# Main.net
KiCad netlist of a schematic drawn in Altium Designer
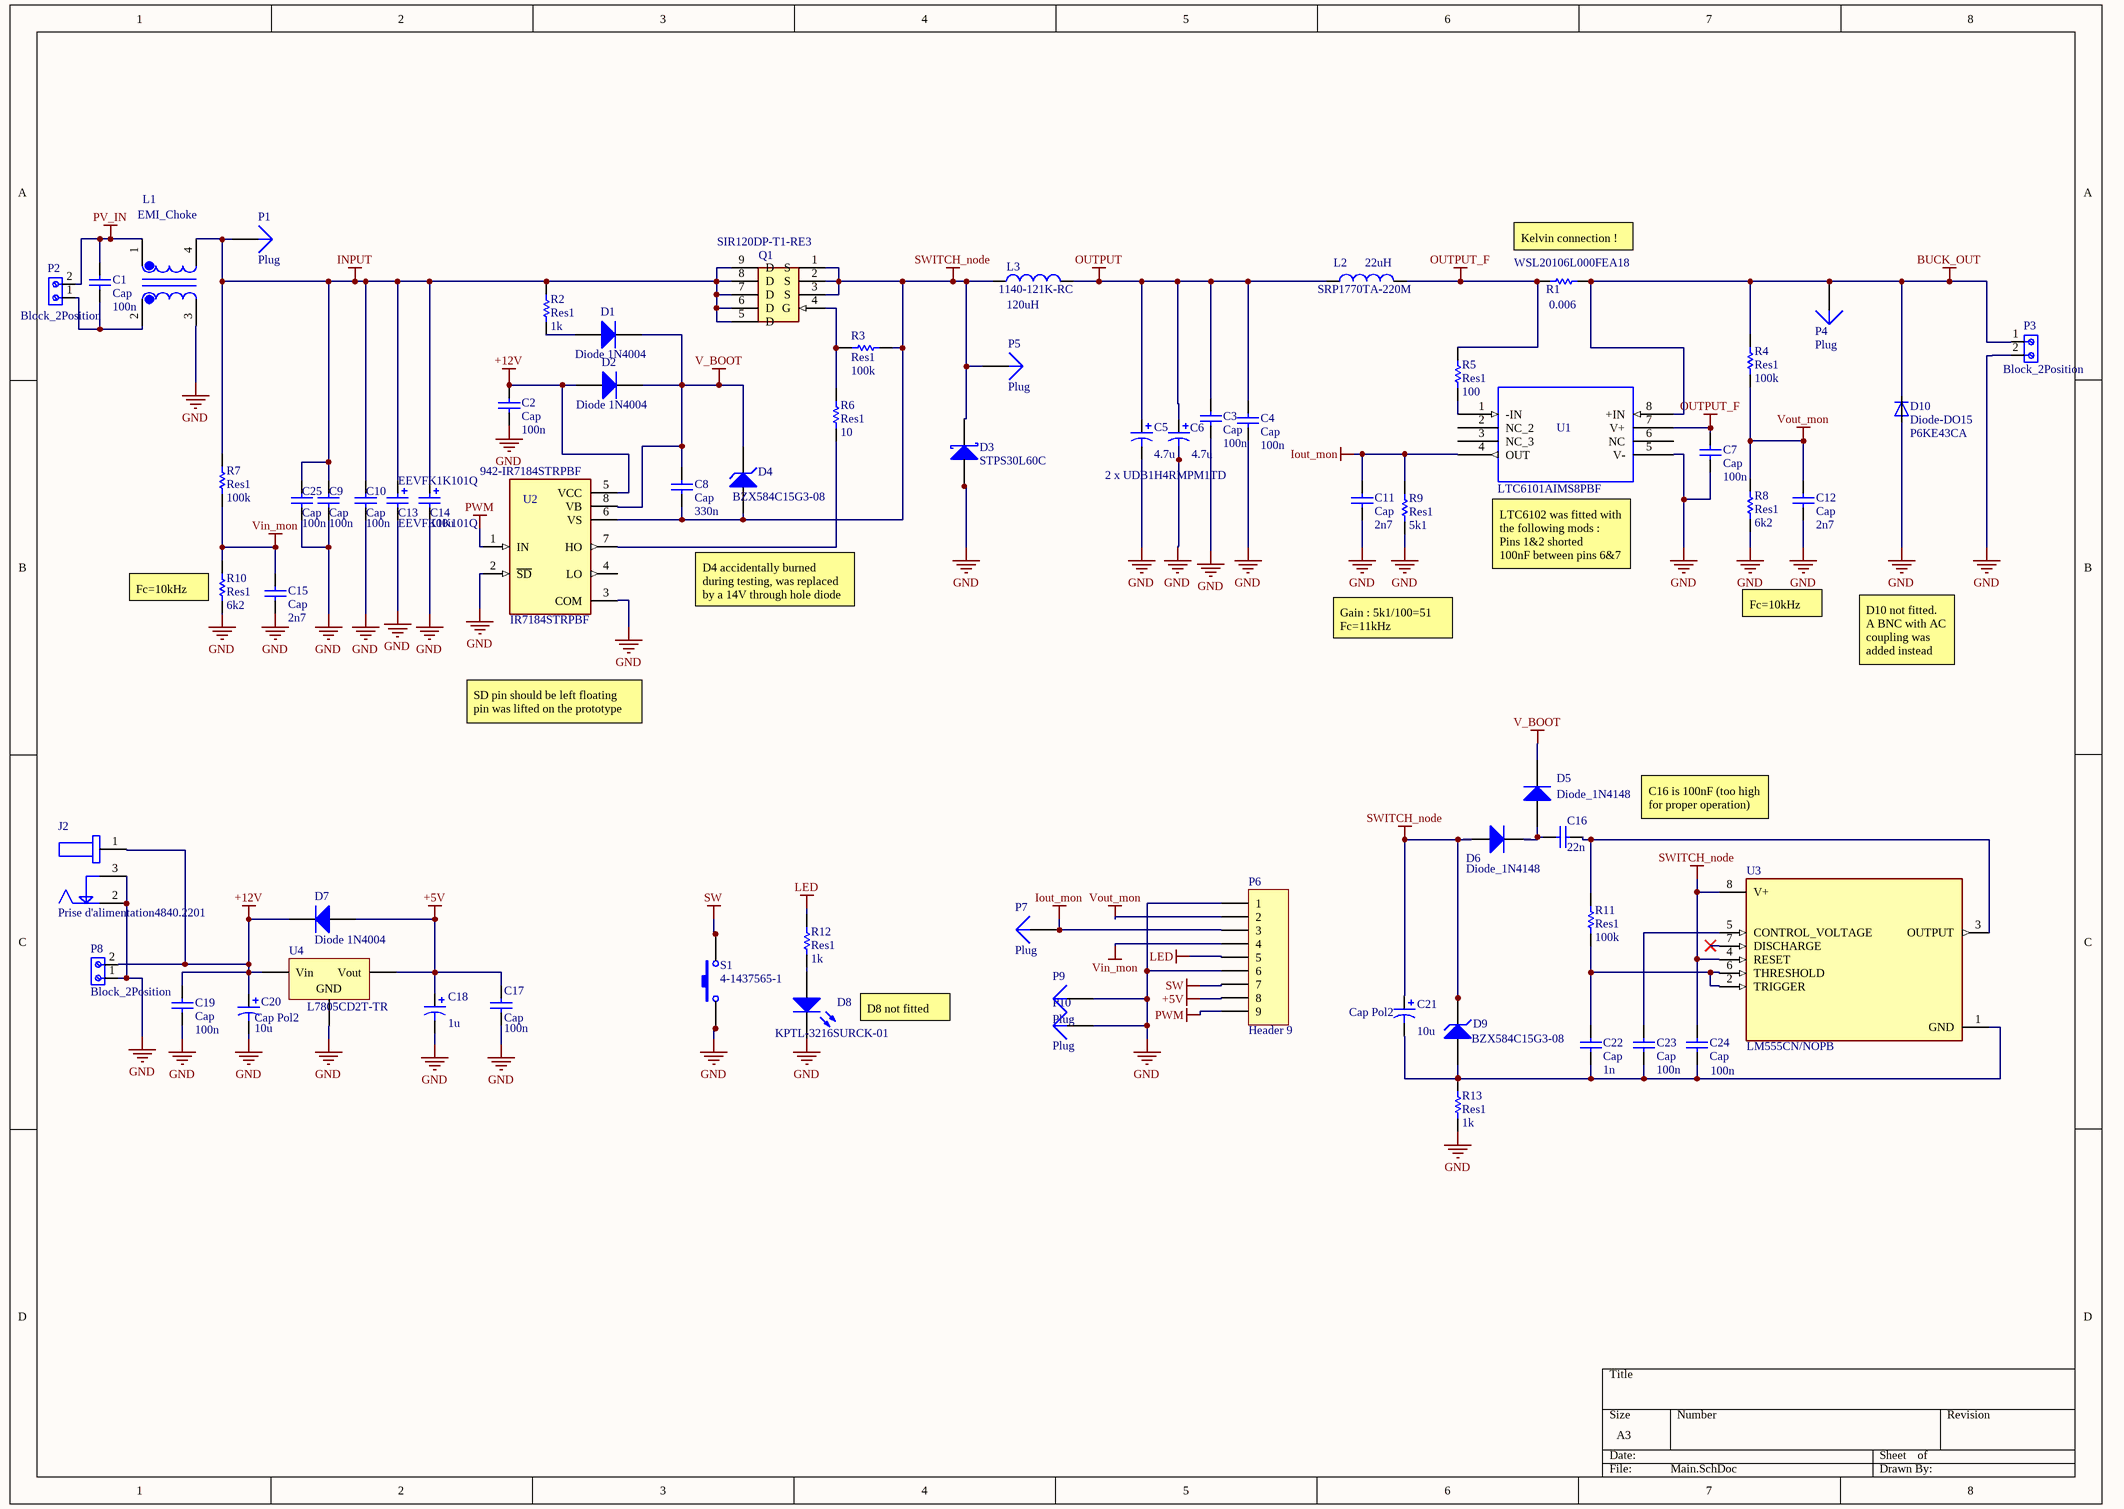
[diagram p0: Main.SchDoc]

(export (version "E")
  (design (tool "Eeschema 10.0.6"))
  (components
    (comp (ref "C1")
      (value "Cap")
      (footprint "C0805")
      (description "Capacitor")
      (fields (field (name "ALTIUM_VALUE") "100n") (field (name "PUBLISHER") "Altium Limited"))
      (libsource (lib "Buck") (part "Cap"))
    )
    (comp (ref "C2")
      (value "Cap")
      (footprint "C0805")
      (description "Capacitor")
      (fields (field (name "ALTIUM_VALUE") "100n") (field (name "PUBLISHER") "Altium Limited"))
      (libsource (lib "Buck") (part "Cap"))
    )
    (comp (ref "C3")
      (value "Cap")
      (footprint "C0805")
      (description "Capacitor")
      (fields (field (name "ALTIUM_VALUE") "100n") (field (name "PUBLISHER") "Altium Limited"))
      (libsource (lib "Buck") (part "Cap"))
    )
    (comp (ref "C4")
      (value "Cap")
      (footprint "C0805")
      (description "Capacitor")
      (fields (field (name "ALTIUM_VALUE") "100n") (field (name "PUBLISHER") "Altium Limited"))
      (libsource (lib "Buck") (part "Cap"))
    )
    (comp (ref "C5")
      (value "4.7u")
      (footprint "C1-C2")
      (fields (field (name "Comment") "2 x UDB1H4RMPM1TD") (field (name "PUBLISHER") "Altium Limited"))
      (libsource (lib "Buck") (part "Cap Pol2"))
    )
    (comp (ref "C6")
      (value "2 x UDB1H4RMPM1TD")
      (footprint "C1-C2")
      (fields (field (name "ALTIUM_VALUE") "4.7u") (field (name "PUBLISHER") "Altium Limited"))
      (libsource (lib "Buck") (part "Cap Pol2"))
    )
    (comp (ref "C7")
      (value "Cap")
      (footprint "C0805")
      (description "Capacitor")
      (fields (field (name "ALTIUM_VALUE") "100n") (field (name "PUBLISHER") "Altium Limited"))
      (libsource (lib "Buck") (part "Cap"))
    )
    (comp (ref "C8")
      (value "Cap")
      (footprint "C0805")
      (description "Capacitor")
      (fields (field (name "ALTIUM_VALUE") "330n") (field (name "PUBLISHER") "Altium Limited"))
      (libsource (lib "Buck") (part "Cap_2"))
    )
    (comp (ref "C9")
      (value "Cap")
      (footprint "C0805")
      (description "Capacitor")
      (fields (field (name "ALTIUM_VALUE") "100n") (field (name "PUBLISHER") "Altium Limited"))
      (libsource (lib "Buck") (part "Cap"))
    )
    (comp (ref "C10")
      (value "Cap")
      (footprint "C0805")
      (description "Capacitor")
      (fields (field (name "ALTIUM_VALUE") "100n") (field (name "PUBLISHER") "Altium Limited"))
      (libsource (lib "Buck") (part "Cap"))
    )
    (comp (ref "C11")
      (value "Cap")
      (footprint "C0805")
      (description "Capacitor")
      (fields (field (name "ALTIUM_VALUE") "2n7") (field (name "PUBLISHER") "Altium Limited"))
      (libsource (lib "Buck") (part "Cap_1"))
    )
    (comp (ref "C12")
      (value "Cap")
      (footprint "C0805")
      (description "Capacitor")
      (fields (field (name "ALTIUM_VALUE") "2n7") (field (name "PUBLISHER") "Altium Limited"))
      (libsource (lib "Buck") (part "Cap_1"))
    )
    (comp (ref "C13")
      (value "EEVFK1K101Q")
      (footprint "C_Pol_EEV-FK1K101Q")
      (description "Polarized Capacitor (Axial)")
      (fields (field (name "PUBLISHER") "Altium Limited"))
      (libsource (lib "Buck") (part "Cap Pol2_1"))
    )
    (comp (ref "C14")
      (value "EEVFK1K101Q")
      (footprint "C_Pol_EEV-FK1K101Q")
      (description "Polarized Capacitor (Axial)")
      (fields (field (name "ALTIUM_VALUE") "100u") (field (name "PUBLISHER") "Altium Limited"))
      (libsource (lib "Buck") (part "Cap Pol2_1"))
    )
    (comp (ref "C15")
      (value "Cap")
      (footprint "C0805")
      (description "Capacitor")
      (fields (field (name "ALTIUM_VALUE") "2n7") (field (name "PUBLISHER") "Altium Limited"))
      (libsource (lib "Buck") (part "Cap_1"))
    )
    (comp (ref "C16") (value "22n") (footprint "C0805") (libsource (lib "Buck") (part "Cap_22n")))
    (comp (ref "C17")
      (value "Cap")
      (footprint "C0805")
      (description "Capacitor")
      (fields (field (name "ALTIUM_VALUE") "100n") (field (name "PUBLISHER") "Altium Limited"))
      (libsource (lib "Buck") (part "Cap"))
    )
    (comp (ref "C18")
      (value "1u")
      (footprint "C0805")
      (fields (field (name "VALEUR") "1u"))
      (libsource (lib "Buck") (part "C_4"))
    )
    (comp (ref "C19")
      (value "Cap")
      (footprint "C0805")
      (description "Capacitor")
      (fields (field (name "ALTIUM_VALUE") "100n") (field (name "PUBLISHER") "Altium Limited"))
      (libsource (lib "Buck") (part "Cap"))
    )
    (comp (ref "C20")
      (value "Cap Pol2")
      (footprint "C_10u")
      (description "Polarized Capacitor (Axial)")
      (fields (field (name "ALTIUM_VALUE") "10u") (field (name "PUBLISHER") "Altium Limited"))
      (libsource (lib "Buck") (part "Cap Pol2_2"))
    )
    (comp (ref "C21")
      (value "Cap Pol2")
      (footprint "C_10u")
      (description "Polarized Capacitor (Axial)")
      (fields (field (name "ALTIUM_VALUE") "10u") (field (name "PUBLISHER") "Altium Limited"))
      (libsource (lib "Buck") (part "Cap Pol2_2"))
    )
    (comp (ref "C22")
      (value "Cap")
      (footprint "C0805")
      (description "Capacitor")
      (fields (field (name "ALTIUM_VALUE") "1n") (field (name "PUBLISHER") "Altium Limited"))
      (libsource (lib "Buck") (part "Cap_3"))
    )
    (comp (ref "C23")
      (value "Cap")
      (footprint "C0805")
      (description "Capacitor")
      (fields (field (name "ALTIUM_VALUE") "100n") (field (name "PUBLISHER") "Altium Limited"))
      (libsource (lib "Buck") (part "Cap"))
    )
    (comp (ref "C24")
      (value "Cap")
      (footprint "C0805")
      (description "Capacitor")
      (fields (field (name "ALTIUM_VALUE") "100n") (field (name "PUBLISHER") "Altium Limited"))
      (libsource (lib "Buck") (part "Cap"))
    )
    (comp (ref "C25")
      (value "Cap")
      (footprint "C0805")
      (description "Capacitor")
      (fields (field (name "ALTIUM_VALUE") "100n") (field (name "PUBLISHER") "Altium Limited"))
      (libsource (lib "Buck") (part "Cap"))
    )
    (comp (ref "D1")
      (value "Diode 1N4004")
      (footprint "diode_1N4004")
      (description "1 Amp General Purpose Rectifier")
      (fields (field (name "PUBLISHER") "Altium Limited"))
      (libsource (lib "Buck") (part "Diode 1N4004"))
    )
    (comp (ref "D2")
      (value "Diode 1N4004")
      (footprint "diode_1N4004")
      (description "1 Amp General Purpose Rectifier")
      (fields (field (name "PUBLISHER") "Altium Limited"))
      (libsource (lib "Buck") (part "Diode 1N4004"))
    )
    (comp (ref "D3")
      (value "STPS30L60C")
      (footprint "Diode_Scho")
      (description "Schottky Diode")
      (fields (field (name "PUBLISHER") "Altium Limited"))
      (libsource (lib "Buck") (part "D Schottky"))
    )
    (comp (ref "D4")
      (value "BZX584C15G3-08")
      (footprint "SOT-523")
      (description "Zener Diode 15V")
      (fields (field (name "PUBLISHER") "Altium Limited"))
      (libsource (lib "Buck") (part "D Zener"))
    )
    (comp (ref "D5")
      (value "Diode_1N4148")
      (footprint "diode_1N4004")
      (libsource (lib "Buck") (part "Diode_1N4148"))
    )
    (comp (ref "D6")
      (value "Diode_1N4148")
      (footprint "diode_1N4004")
      (libsource (lib "Buck") (part "Diode_1N4148"))
    )
    (comp (ref "D7")
      (value "Diode 1N4004")
      (footprint "diode_1N4004")
      (description "1 Amp General Purpose Rectifier")
      (fields (field (name "PUBLISHER") "Altium Limited"))
      (libsource (lib "Buck") (part "Diode 1N4004"))
    )
    (comp (ref "D8")
      (value "KPTL-3216SURCK-01")
      (footprint "LED")
      (description "Typical RED, GREEN, YELLOW, AMBER GaAs LED")
      (fields (field (name "PUBLISHER") "Altium Limited"))
      (libsource (lib "Buck") (part "LED2"))
    )
    (comp (ref "D9")
      (value "BZX584C15G3-08")
      (footprint "SOT-523")
      (description "Zener Diode 15V")
      (fields (field (name "PUBLISHER") "Altium Limited"))
      (libsource (lib "Buck") (part "D Zener"))
    )
    (comp (ref "D10")
      (value "Diode-DO15")
      (footprint "DO15")
      (description "P6KE43CA")
      (fields (field (name "REF") "P6KE43CA"))
      (libsource (lib "Buck") (part "Diode-DO15"))
    )
    (comp (ref "J2")
      (value "Prise d'alimentation4840.2201")
      (footprint "Prise d'alimentation4840.2201")
      (libsource (lib "Buck") (part "Prise d'alimentation4840.2201"))
    )
    (comp (ref "L1")
      (value "EMI_Choke")
      (footprint "EMI_Choke")
      (description "1mH 20A")
      (libsource (lib "Buck") (part "EMI_Choke"))
    )
    (comp (ref "L2")
      (value "SRP1770TA-220M")
      (footprint "SRP1770TA-220M")
      (fields (field (name "ALTIUM_VALUE") "22uH"))
      (libsource (lib "Buck") (part "SRP1770TA-220M"))
    )
    (comp (ref "L3")
      (value "1140-121K-RC")
      (footprint "L_120")
      (fields (field (name "ALTIUM_VALUE") "120uH") (field (name "PUBLISHER") "Altium Limited"))
      (libsource (lib "Buck") (part "Inductor"))
    )
    (comp (ref "P1")
      (value "Plug")
      (footprint "PIN1")
      (fields (field (name "PUBLISHER") "Altium Limited"))
      (libsource (lib "Miscellaneous Connectors") (part "Plug"))
    )
    (comp (ref "P2")
      (value "Block_2Position")
      (footprint "Block_2Position")
      (libsource (lib "Buck") (part "Block_2Position"))
    )
    (comp (ref "P3")
      (value "Block_2Position")
      (footprint "Block_2Position")
      (libsource (lib "Buck") (part "Block_2Position"))
    )
    (comp (ref "P4")
      (value "Plug")
      (footprint "PIN1")
      (fields (field (name "PUBLISHER") "Altium Limited"))
      (libsource (lib "Miscellaneous Connectors") (part "Plug"))
    )
    (comp (ref "P5")
      (value "Plug")
      (footprint "PIN1")
      (fields (field (name "PUBLISHER") "Altium Limited"))
      (libsource (lib "Miscellaneous Connectors") (part "Plug"))
    )
    (comp (ref "P6")
      (value "Header 9")
      (footprint "HDR1X9")
      (description "Header, 9-Pin")
      (fields (field (name "PUBLISHER") "Altium Limited"))
      (libsource (lib "Buck") (part "Header 9"))
    )
    (comp (ref "P7")
      (value "Plug")
      (footprint "PIN1")
      (fields (field (name "PUBLISHER") "Altium Limited"))
      (libsource (lib "Miscellaneous Connectors") (part "Plug"))
    )
    (comp (ref "P8")
      (value "Block_2Position")
      (footprint "Block_2Position")
      (libsource (lib "Buck") (part "Block_2Position"))
    )
    (comp (ref "P9")
      (value "Plug")
      (footprint "PIN1")
      (fields (field (name "PUBLISHER") "Altium Limited"))
      (libsource (lib "Miscellaneous Connectors") (part "Plug"))
    )
    (comp (ref "P10")
      (value "Plug")
      (footprint "PIN1")
      (fields (field (name "PUBLISHER") "Altium Limited"))
      (libsource (lib "Miscellaneous Connectors") (part "Plug"))
    )
    (comp (ref "Q1")
      (value "SIR120DP-T1-RE3")
      (footprint "MOFET_SIR120DP-T1-RE3")
      (libsource (lib "Buck") (part "SIR120DP-T1-RE3"))
    )
    (comp (ref "R1")
      (value "WSL20106L000FEA18")
      (footprint "R0.006")
      (description "Resistor")
      (fields (field (name "ALTIUM_VALUE") "0.006") (field (name "PUBLISHER") "Altium Limited"))
      (libsource (lib "Buck") (part "Res1_2"))
    )
    (comp (ref "R2")
      (value "Res1")
      (footprint "R0805")
      (description "Resistor")
      (fields (field (name "ALTIUM_VALUE") "1k") (field (name "PUBLISHER") "Altium Limited"))
      (libsource (lib "Buck") (part "Res1_6"))
    )
    (comp (ref "R3")
      (value "Res1")
      (footprint "R0805")
      (description "Resistor")
      (fields (field (name "ALTIUM_VALUE") "100k") (field (name "PUBLISHER") "Altium Limited"))
      (libsource (lib "Buck") (part "Res1"))
    )
    (comp (ref "R4")
      (value "Res1")
      (footprint "R0805")
      (description "Resistor")
      (fields (field (name "ALTIUM_VALUE") "100k") (field (name "PUBLISHER") "Altium Limited"))
      (libsource (lib "Buck") (part "Res1"))
    )
    (comp (ref "R5")
      (value "Res1")
      (footprint "R0805")
      (description "Resistor")
      (fields (field (name "ALTIUM_VALUE") "100") (field (name "PUBLISHER") "Altium Limited"))
      (libsource (lib "Buck") (part "Res1_3"))
    )
    (comp (ref "R6")
      (value "Res1")
      (footprint "R0805")
      (description "Resistor")
      (fields (field (name "ALTIUM_VALUE") "10") (field (name "PUBLISHER") "Altium Limited"))
      (libsource (lib "Buck") (part "Res1_5"))
    )
    (comp (ref "R7")
      (value "Res1")
      (footprint "R0805")
      (description "Resistor")
      (fields (field (name "ALTIUM_VALUE") "100k") (field (name "PUBLISHER") "Altium Limited"))
      (libsource (lib "Buck") (part "Res1"))
    )
    (comp (ref "R8")
      (value "Res1")
      (footprint "R0805")
      (description "Resistor")
      (fields (field (name "ALTIUM_VALUE") "6k2") (field (name "PUBLISHER") "Altium Limited"))
      (libsource (lib "Buck") (part "Res1_1"))
    )
    (comp (ref "R9")
      (value "Res1")
      (footprint "R0805")
      (description "Resistor")
      (fields (field (name "ALTIUM_VALUE") "5k1") (field (name "PUBLISHER") "Altium Limited"))
      (libsource (lib "Buck") (part "Res1_4"))
    )
    (comp (ref "R10")
      (value "Res1")
      (footprint "R0805")
      (description "Resistor")
      (fields (field (name "ALTIUM_VALUE") "6k2") (field (name "PUBLISHER") "Altium Limited"))
      (libsource (lib "Buck") (part "Res1_1"))
    )
    (comp (ref "R11")
      (value "Res1")
      (footprint "R0805")
      (description "Resistor")
      (fields (field (name "ALTIUM_VALUE") "100k") (field (name "PUBLISHER") "Altium Limited"))
      (libsource (lib "Buck") (part "Res1"))
    )
    (comp (ref "R12")
      (value "Res1")
      (footprint "R0805")
      (description "Resistor")
      (fields (field (name "ALTIUM_VALUE") "1k") (field (name "PUBLISHER") "Altium Limited"))
      (libsource (lib "Buck") (part "Res1_6"))
    )
    (comp (ref "R13")
      (value "Res1")
      (footprint "R0805")
      (description "Resistor")
      (fields (field (name "ALTIUM_VALUE") "1k") (field (name "PUBLISHER") "Altium Limited"))
      (libsource (lib "Buck") (part "Res1_6"))
    )
    (comp (ref "S1")
      (value "4-1437565-1")
      (footprint "Switch")
      (description "Switch")
      (fields (field (name "PUBLISHER") "Altium Limited"))
      (libsource (lib "Buck") (part "SW-PB"))
    )
    (comp (ref "U1")
      (value "LTC6101AIMS8PBF")
      (footprint "LTC6101AIMS8#PBF")
      (description "SP Amp Current Sense Amp Single 60V Automotive 8-Pin MSOP Tube")
      (fields (field (name "MP") "LTC6101AIMS8#PBF") (field (name "MF") "Analog Devices"))
      (libsource (lib "Buck") (part "LTC6101AIMS8PBF"))
    )
    (comp (ref "U2")
      (value "IR7184STRPBF")
      (footprint "IR7184STRPBF")
      (fields
        (field (name "MF") "Infineon Technologies")
        (field (name "SUPPLIER PART NUMBER 1") "942-IR7184STRPBF")
      )
      (libsource (lib "Buck") (part "IR7184STRPBF"))
    )
    (comp (ref "U3")
      (value "LM555CN/NOPB")
      (footprint "LM555CN/NOPB")
      (libsource (lib "Buck") (part "LM555CN/NOPB"))
    )
    (comp (ref "U4")
      (value "L7805CD2T-TR")
      (footprint "Volt_Reg")
      (description "Voltage Regulator")
      (fields (field (name "PUBLISHER") "Altium Limited"))
      (libsource (lib "Buck") (part "Volt Reg"))
    )
  )
  (nets
    (net (code "1") (name "+5V") (class "Default")
      (node (ref "C17") (pin "2") (pinfunction "2_2") (pintype "passive"))
      (node (ref "C18") (pin "1") (pinfunction "1_1") (pintype "passive"))
      (node (ref "D7") (pin "A") (pinfunction "A_A") (pintype "passive"))
      (node (ref "P6") (pin "8") (pinfunction "8_8") (pintype "passive"))
      (node (ref "U4") (pin "3") (pinfunction "Vout_3") (pintype "passive"))
    )
    (net (code "2") (name "+12V") (class "Default")
      (node (ref "C19") (pin "2") (pinfunction "2_2") (pintype "passive"))
      (node (ref "C2") (pin "2") (pinfunction "2_2") (pintype "passive"))
      (node (ref "C20") (pin "1") (pinfunction "1_1") (pintype "passive"))
      (node (ref "D2") (pin "A") (pinfunction "A_A") (pintype "passive"))
      (node (ref "D7") (pin "C") (pinfunction "K_C") (pintype "passive"))
      (node (ref "J2") (pin "1") (pinfunction "1_1") (pintype "passive"))
      (node (ref "P8") (pin "2") (pinfunction "2_2") (pintype "passive"))
      (node (ref "U2") (pin "5") (pinfunction "VCC_5") (pintype "power_in"))
      (node (ref "U4") (pin "1") (pinfunction "Vin_1") (pintype "passive"))
    )
    (net (code "3") (name "BUCK_OUT") (class "Default")
      (node (ref "D10") (pin "C") (pinfunction "C_C") (pintype "passive"))
      (node (ref "P3") (pin "1") (pinfunction "1_1") (pintype "passive"))
      (node (ref "P4") (pin "1") (pinfunction "1_1") (pintype "passive"))
      (node (ref "R1") (pin "1") (pinfunction "1_1") (pintype "passive"))
      (node (ref "R4") (pin "2") (pinfunction "2_2") (pintype "passive"))
      (node (ref "U1") (pin "8") (pinfunction "+IN_8") (pintype "input"))
    )
    (net (code "4") (name "GND") (class "Default")
      (node (ref "C10") (pin "1") (pinfunction "1_1") (pintype "passive"))
      (node (ref "C11") (pin "1") (pinfunction "1_1") (pintype "passive"))
      (node (ref "C12") (pin "1") (pinfunction "1_1") (pintype "passive"))
      (node (ref "C13") (pin "2") (pinfunction "2_2") (pintype "passive"))
      (node (ref "C14") (pin "2") (pinfunction "2_2") (pintype "passive"))
      (node (ref "C15") (pin "1") (pinfunction "1_1") (pintype "passive"))
      (node (ref "C17") (pin "1") (pinfunction "1_1") (pintype "passive"))
      (node (ref "C18") (pin "2") (pinfunction "2_2") (pintype "passive"))
      (node (ref "C19") (pin "1") (pinfunction "1_1") (pintype "passive"))
      (node (ref "C2") (pin "1") (pinfunction "1_1") (pintype "passive"))
      (node (ref "C20") (pin "2") (pinfunction "2_2") (pintype "passive"))
      (node (ref "C25") (pin "1") (pinfunction "1_1") (pintype "passive"))
      (node (ref "C3") (pin "1") (pinfunction "1_1") (pintype "passive"))
      (node (ref "C4") (pin "1") (pinfunction "1_1") (pintype "passive"))
      (node (ref "C5") (pin "2") (pinfunction "2_2") (pintype "passive"))
      (node (ref "C6") (pin "2") (pinfunction "2_2") (pintype "passive"))
      (node (ref "C7") (pin "1") (pinfunction "1_1") (pintype "passive"))
      (node (ref "C9") (pin "1") (pinfunction "1_1") (pintype "passive"))
      (node (ref "D10") (pin "A") (pinfunction "A_A") (pintype "passive"))
      (node (ref "D3") (pin "1") (pinfunction "A_1") (pintype "passive"))
      (node (ref "D3") (pin "3") (pinfunction "3_3") (pintype "passive"))
      (node (ref "D8") (pin "2") (pinfunction "K_2") (pintype "passive"))
      (node (ref "J2") (pin "2") (pinfunction "2_2") (pintype "passive"))
      (node (ref "J2") (pin "3") (pinfunction "3_3") (pintype "passive"))
      (node (ref "L1") (pin "3") (pinfunction "3_3") (pintype "passive"))
      (node (ref "P10") (pin "1") (pinfunction "1_1") (pintype "passive"))
      (node (ref "P3") (pin "2") (pinfunction "2_2") (pintype "passive"))
      (node (ref "P6") (pin "1") (pinfunction "1_1") (pintype "passive"))
      (node (ref "P6") (pin "6") (pinfunction "6_6") (pintype "passive"))
      (node (ref "P8") (pin "1") (pinfunction "1_1") (pintype "passive"))
      (node (ref "P9") (pin "1") (pinfunction "1_1") (pintype "passive"))
      (node (ref "R10") (pin "1") (pinfunction "1_1") (pintype "passive"))
      (node (ref "R13") (pin "2") (pinfunction "2_2") (pintype "passive"))
      (node (ref "R8") (pin "1") (pinfunction "1_1") (pintype "passive"))
      (node (ref "R9") (pin "1") (pinfunction "1_1") (pintype "passive"))
      (node (ref "S1") (pin "1") (pinfunction "1_1") (pintype "passive"))
      (node (ref "S1") (pin "2") (pinfunction "2_2") (pintype "passive"))
      (node (ref "U1") (pin "5") (pinfunction "V-_5") (pintype "power_in"))
      (node (ref "U2") (pin "2") (pinfunction "~{SD}_2") (pintype "input"))
      (node (ref "U2") (pin "3") (pinfunction "COM_3") (pintype "power_in"))
      (node (ref "U4") (pin "4") (pinfunction "GND_4") (pintype "passive"))
    )
    (net (code "5") (name "INPUT") (class "Default")
      (node (ref "C10") (pin "2") (pinfunction "2_2") (pintype "passive"))
      (node (ref "C13") (pin "1") (pinfunction "1_1") (pintype "passive"))
      (node (ref "C14") (pin "1") (pinfunction "1_1") (pintype "passive"))
      (node (ref "C25") (pin "2") (pinfunction "2_2") (pintype "passive"))
      (node (ref "C9") (pin "2") (pinfunction "2_2") (pintype "passive"))
      (node (ref "L1") (pin "4") (pinfunction "4_4") (pintype "passive"))
      (node (ref "P1") (pin "1") (pinfunction "1_1") (pintype "passive"))
      (node (ref "Q1") (pin "5") (pinfunction "D_5") (pintype "power_in"))
      (node (ref "Q1") (pin "6") (pinfunction "D_6") (pintype "power_in"))
      (node (ref "Q1") (pin "7") (pinfunction "D_7") (pintype "power_in"))
      (node (ref "Q1") (pin "8") (pinfunction "D_8") (pintype "power_in"))
      (node (ref "Q1") (pin "9") (pinfunction "D_9") (pintype "power_in"))
      (node (ref "R2") (pin "1") (pinfunction "1_1") (pintype "passive"))
      (node (ref "R7") (pin "2") (pinfunction "2_2") (pintype "passive"))
    )
    (net (code "6") (name "Iout_mon") (class "Default")
      (node (ref "C11") (pin "2") (pinfunction "2_2") (pintype "passive"))
      (node (ref "P6") (pin "3") (pinfunction "3_3") (pintype "passive"))
      (node (ref "P7") (pin "1") (pinfunction "1_1") (pintype "passive"))
      (node (ref "R9") (pin "2") (pinfunction "2_2") (pintype "passive"))
      (node (ref "U1") (pin "4") (pinfunction "OUT_4") (pintype "output"))
    )
    (net (code "7") (name "LED") (class "Default")
      (node (ref "P6") (pin "5") (pinfunction "5_5") (pintype "passive"))
      (node (ref "R12") (pin "1") (pinfunction "1_1") (pintype "passive"))
    )
    (net (code "8") (name "Net-(C1-Pad1)") (class "Default")
      (node (ref "C1") (pin "1") (pinfunction "1_1") (pintype "passive"))
      (node (ref "L1") (pin "2") (pinfunction "2_2") (pintype "passive"))
      (node (ref "P2") (pin "1") (pinfunction "1_1") (pintype "passive"))
    )
    (net (code "9") (name "Net-(C16-Pad2)") (class "Default")
      (node (ref "C16") (pin "2") (pinfunction "2_2") (pintype "passive"))
      (node (ref "D5") (pin "A") (pinfunction "A_A") (pintype "passive"))
      (node (ref "D6") (pin "C") (pinfunction "C_C") (pintype "passive"))
    )
    (net (code "10") (name "Net-(D1-PadA)") (class "Default")
      (node (ref "D1") (pin "A") (pinfunction "A_A") (pintype "passive"))
      (node (ref "R2") (pin "2") (pinfunction "2_2") (pintype "passive"))
    )
    (net (code "11") (name "Net-(D8-A)") (class "Default")
      (node (ref "D8") (pin "1") (pinfunction "A_1") (pintype "passive"))
      (node (ref "R12") (pin "2") (pinfunction "2_2") (pintype "passive"))
    )
    (net (code "12") (name "Net-(Q1-G)") (class "Default")
      (node (ref "Q1") (pin "4") (pinfunction "G_4") (pintype "input"))
      (node (ref "R3") (pin "2") (pinfunction "2_2") (pintype "passive"))
      (node (ref "R6") (pin "2") (pinfunction "2_2") (pintype "passive"))
    )
    (net (code "13") (name "Net-(U1--IN)") (class "Default")
      (node (ref "R5") (pin "1") (pinfunction "1_1") (pintype "passive"))
      (node (ref "U1") (pin "1") (pinfunction "-IN_1") (pintype "input"))
    )
    (net (code "14") (name "Net-(U2-HO)") (class "Default")
      (node (ref "R6") (pin "1") (pinfunction "1_1") (pintype "passive"))
      (node (ref "U2") (pin "7") (pinfunction "HO_7") (pintype "output"))
    )
    (net (code "15") (name "Net-(U3-CONTROL_VOLTAGE)") (class "Default")
      (node (ref "C23") (pin "2") (pinfunction "2_2") (pintype "passive"))
      (node (ref "U3") (pin "5") (pinfunction "CONTROL_VOLTAGE_5") (pintype "input"))
    )
    (net (code "16") (name "Net-(U3-GND)") (class "Default")
      (node (ref "C21") (pin "2") (pinfunction "2_2") (pintype "passive"))
      (node (ref "C22") (pin "1") (pinfunction "1_1") (pintype "passive"))
      (node (ref "C23") (pin "1") (pinfunction "1_1") (pintype "passive"))
      (node (ref "C24") (pin "1") (pinfunction "1_1") (pintype "passive"))
      (node (ref "D9") (pin "1") (pinfunction "1_1") (pintype "passive"))
      (node (ref "R13") (pin "1") (pinfunction "1_1") (pintype "passive"))
      (node (ref "U3") (pin "1") (pinfunction "GND_1") (pintype "power_in"))
    )
    (net (code "17") (name "Net-(U3-OUTPUT)") (class "Default")
      (node (ref "C16") (pin "1") (pinfunction "1_1") (pintype "passive"))
      (node (ref "R11") (pin "2") (pinfunction "2_2") (pintype "passive"))
      (node (ref "U3") (pin "3") (pinfunction "OUTPUT_3") (pintype "output"))
    )
    (net (code "18") (name "Net-(U3-THRESHOLD)") (class "Default")
      (node (ref "C22") (pin "2") (pinfunction "2_2") (pintype "passive"))
      (node (ref "R11") (pin "1") (pinfunction "1_1") (pintype "passive"))
      (node (ref "U3") (pin "2") (pinfunction "TRIGGER_2") (pintype "input"))
      (node (ref "U3") (pin "6") (pinfunction "THRESHOLD_6") (pintype "input"))
    )
    (net (code "19") (name "OUTPUT") (class "Default")
      (node (ref "C3") (pin "2") (pinfunction "2_2") (pintype "passive"))
      (node (ref "C4") (pin "2") (pinfunction "2_2") (pintype "passive"))
      (node (ref "C5") (pin "1") (pinfunction "1_1") (pintype "passive"))
      (node (ref "C6") (pin "1") (pinfunction "1_1") (pintype "passive"))
      (node (ref "L2") (pin "1") (pinfunction "1_1") (pintype "passive"))
      (node (ref "L3") (pin "2") (pinfunction "2_2") (pintype "passive"))
    )
    (net (code "20") (name "OUTPUT_F") (class "Default")
      (node (ref "C7") (pin "2") (pinfunction "2_2") (pintype "passive"))
      (node (ref "L2") (pin "2") (pinfunction "2_2") (pintype "passive"))
      (node (ref "R1") (pin "2") (pinfunction "2_2") (pintype "passive"))
      (node (ref "R5") (pin "2") (pinfunction "2_2") (pintype "passive"))
      (node (ref "U1") (pin "7") (pinfunction "V+_7") (pintype "power_in"))
    )
    (net (code "21") (name "PV_IN") (class "Default")
      (node (ref "C1") (pin "2") (pinfunction "2_2") (pintype "passive"))
      (node (ref "L1") (pin "1") (pinfunction "1_1") (pintype "passive"))
      (node (ref "P2") (pin "2") (pinfunction "2_2") (pintype "passive"))
    )
    (net (code "22") (name "PWM") (class "Default")
      (node (ref "P6") (pin "9") (pinfunction "9_9") (pintype "passive"))
      (node (ref "U2") (pin "1") (pinfunction "IN_1") (pintype "input"))
    )
    (net (code "23") (name "SW") (class "Default")
      (node (ref "P6") (pin "7") (pinfunction "7_7") (pintype "passive"))
      (node (ref "S1") (pin "3") (pinfunction "3_3") (pintype "passive"))
      (node (ref "S1") (pin "4") (pinfunction "4_4") (pintype "passive"))
    )
    (net (code "24") (name "SWITCH_node") (class "Default")
      (node (ref "C21") (pin "1") (pinfunction "1_1") (pintype "passive"))
      (node (ref "C24") (pin "2") (pinfunction "2_2") (pintype "passive"))
      (node (ref "C8") (pin "1") (pinfunction "1_1") (pintype "passive"))
      (node (ref "D3") (pin "4") (pinfunction "K_4") (pintype "passive"))
      (node (ref "D4") (pin "1") (pinfunction "1_1") (pintype "passive"))
      (node (ref "D6") (pin "A") (pinfunction "A_A") (pintype "passive"))
      (node (ref "D9") (pin "2") (pinfunction "2_2") (pintype "passive"))
      (node (ref "L3") (pin "1") (pinfunction "1_1") (pintype "passive"))
      (node (ref "P5") (pin "1") (pinfunction "1_1") (pintype "passive"))
      (node (ref "Q1") (pin "1") (pinfunction "S_1") (pintype "power_in"))
      (node (ref "Q1") (pin "2") (pinfunction "S_2") (pintype "power_in"))
      (node (ref "Q1") (pin "3") (pinfunction "S_3") (pintype "power_in"))
      (node (ref "R3") (pin "1") (pinfunction "1_1") (pintype "passive"))
      (node (ref "U2") (pin "6") (pinfunction "VS_6") (pintype "power_in"))
      (node (ref "U3") (pin "4") (pinfunction "RESET_4") (pintype "input"))
      (node (ref "U3") (pin "8") (pinfunction "V+_8") (pintype "power_in"))
    )
    (net (code "25") (name "V_BOOT") (class "Default")
      (node (ref "C8") (pin "2") (pinfunction "2_2") (pintype "passive"))
      (node (ref "D1") (pin "C") (pinfunction "K_C") (pintype "passive"))
      (node (ref "D2") (pin "C") (pinfunction "K_C") (pintype "passive"))
      (node (ref "D4") (pin "2") (pinfunction "2_2") (pintype "passive"))
      (node (ref "D5") (pin "C") (pinfunction "C_C") (pintype "passive"))
      (node (ref "U2") (pin "8") (pinfunction "VB_8") (pintype "power_in"))
    )
    (net (code "26") (name "Vin_mon") (class "Default")
      (node (ref "C15") (pin "2") (pinfunction "2_2") (pintype "passive"))
      (node (ref "P6") (pin "4") (pinfunction "4_4") (pintype "passive"))
      (node (ref "R10") (pin "2") (pinfunction "2_2") (pintype "passive"))
      (node (ref "R7") (pin "1") (pinfunction "1_1") (pintype "passive"))
    )
    (net (code "27") (name "Vout_mon") (class "Default")
      (node (ref "C12") (pin "2") (pinfunction "2_2") (pintype "passive"))
      (node (ref "P6") (pin "2") (pinfunction "2_2") (pintype "passive"))
      (node (ref "R4") (pin "1") (pinfunction "1_1") (pintype "passive"))
      (node (ref "R8") (pin "2") (pinfunction "2_2") (pintype "passive"))
    )
    (net (code "28") (name "unconnected-(U1-NC-Pad6)") (class "Default")
      (node (ref "U1") (pin "6") (pinfunction "NC_6") (pintype "passive"))
    )
    (net (code "29") (name "unconnected-(U1-NC_2-Pad2)") (class "Default")
      (node (ref "U1") (pin "2") (pinfunction "NC_2_2") (pintype "passive"))
    )
    (net (code "30") (name "unconnected-(U1-NC_3-Pad3)") (class "Default")
      (node (ref "U1") (pin "3") (pinfunction "NC_3_3") (pintype "passive"))
    )
    (net (code "31") (name "unconnected-(U2-LO-Pad4)") (class "Default")
      (node (ref "U2") (pin "4") (pinfunction "LO_4") (pintype "output"))
    )
    (net (code "32") (name "unconnected-(U3-DISCHARGE-Pad7)") (class "Default")
      (node (ref "U3") (pin "7") (pinfunction "DISCHARGE_7") (pintype "input+no_connect"))
    )
  )
)
